# power_driver.net
KiCad netlist of a schematic drawn in EAGLE
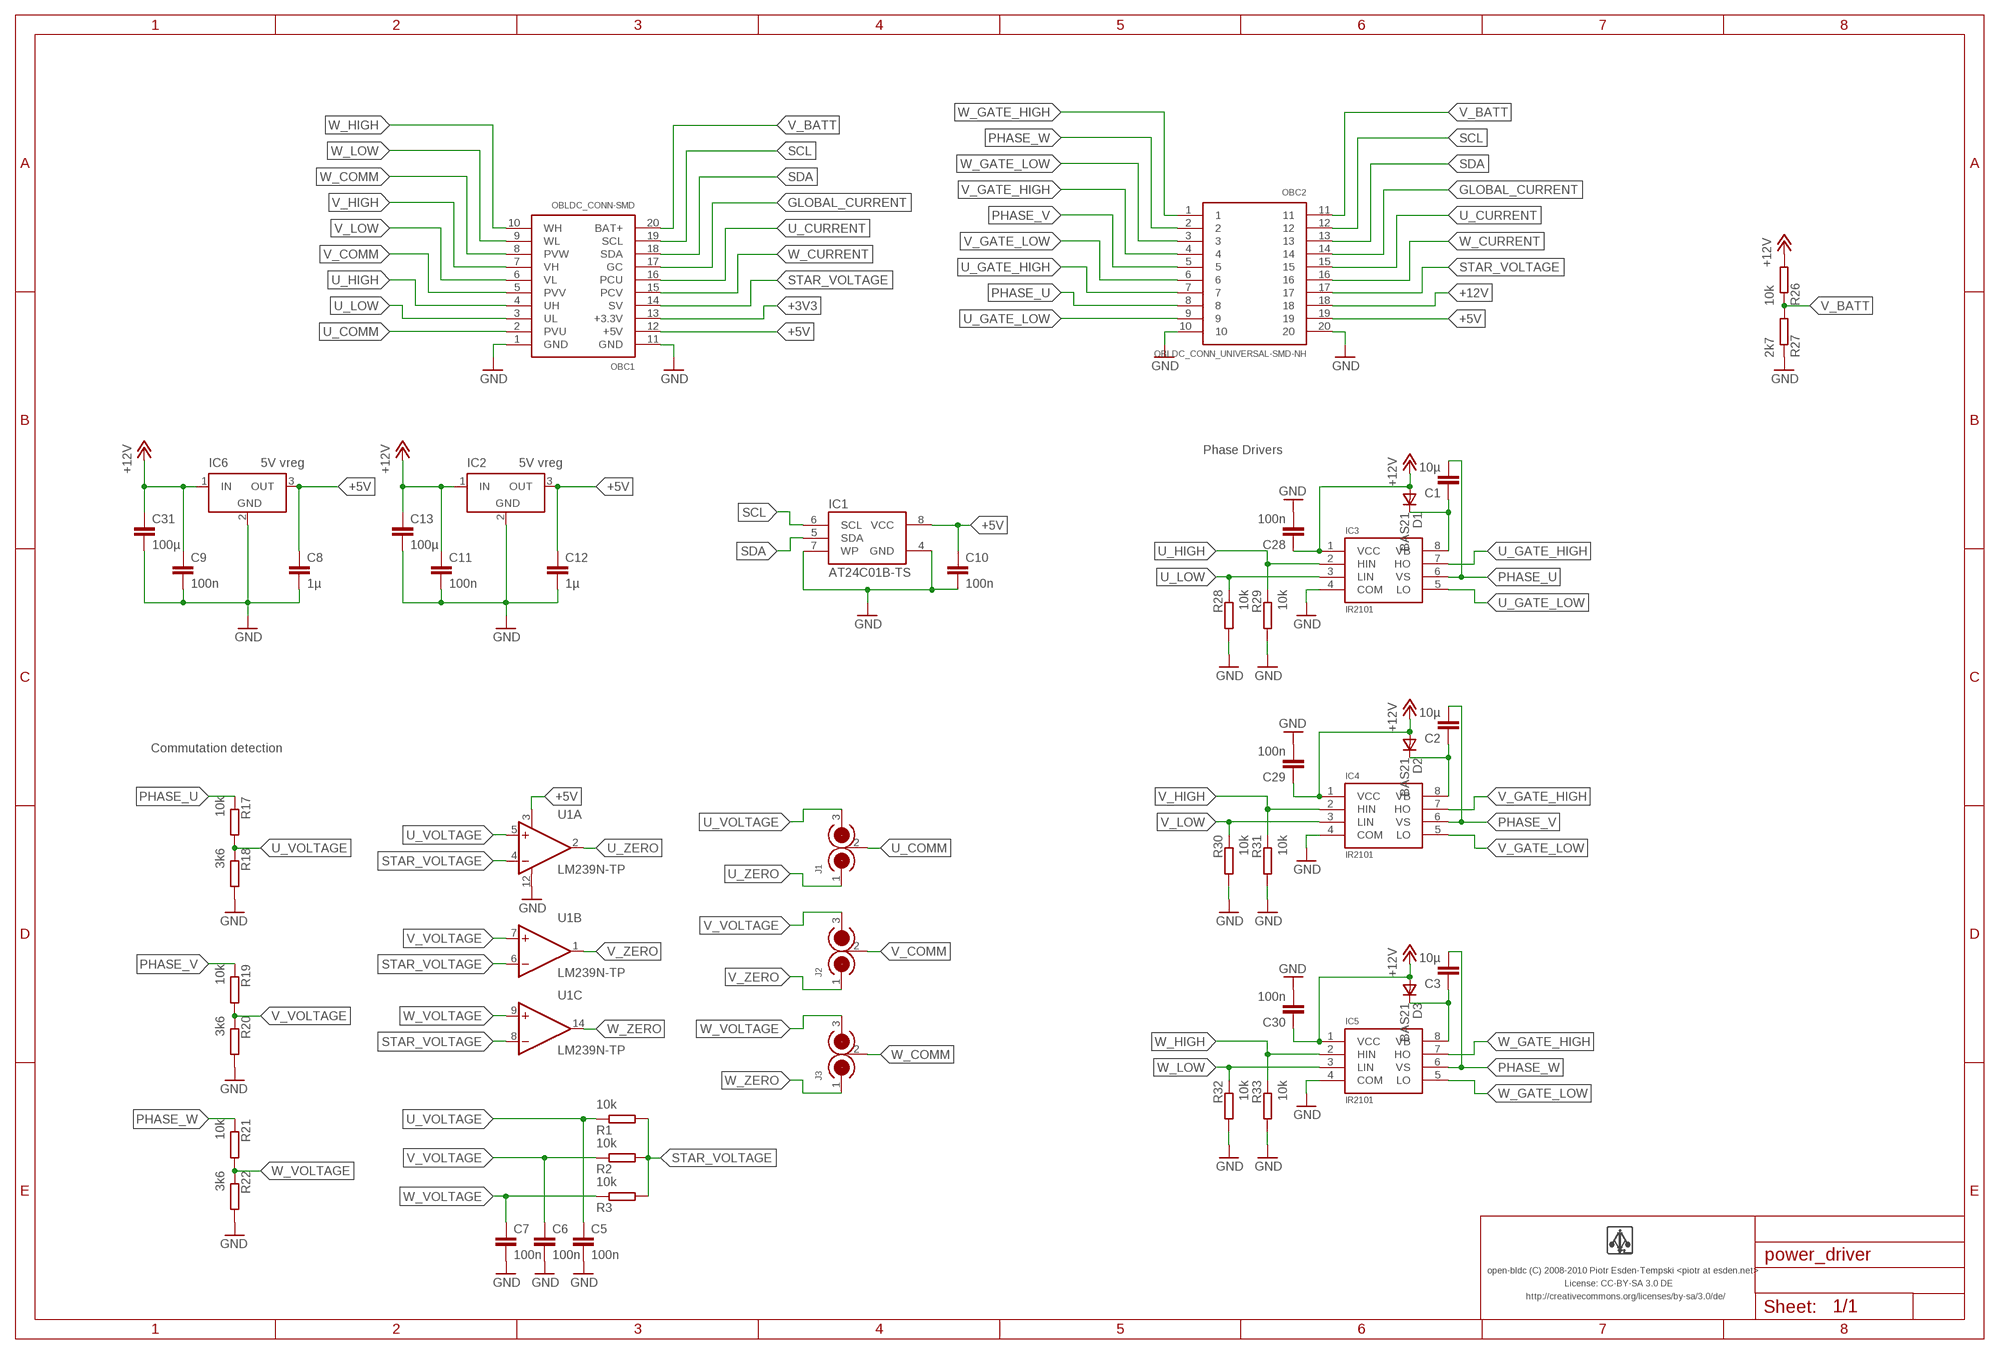
[diagram p0: schematic, sheet 1]

(export (version "E")
  (design (tool "Eeschema 10.0.6"))
  (components
    (comp (ref "C1")
      (value "10µ")
      (footprint "eagle-import:0603-CAP")
      (libsource (lib "eagle-import") (part "CAPACITOR-0603"))
    )
    (comp (ref "C2")
      (value "10µ")
      (footprint "eagle-import:0603-CAP")
      (libsource (lib "eagle-import") (part "CAPACITOR-0603"))
    )
    (comp (ref "C3")
      (value "10µ")
      (footprint "eagle-import:0603-CAP")
      (libsource (lib "eagle-import") (part "CAPACITOR-0603"))
    )
    (comp (ref "C5")
      (value "100n")
      (footprint "eagle-import:0603-CAP")
      (libsource (lib "eagle-import") (part "CAPACITOR-0603"))
    )
    (comp (ref "C6")
      (value "100n")
      (footprint "eagle-import:0603-CAP")
      (libsource (lib "eagle-import") (part "CAPACITOR-0603"))
    )
    (comp (ref "C7")
      (value "100n")
      (footprint "eagle-import:0603-CAP")
      (libsource (lib "eagle-import") (part "CAPACITOR-0603"))
    )
    (comp (ref "C8")
      (value "1µ")
      (footprint "eagle-import:0603-CAP")
      (libsource (lib "eagle-import") (part "CAPACITOR-0603"))
    )
    (comp (ref "C9")
      (value "100n")
      (footprint "eagle-import:0603-CAP")
      (libsource (lib "eagle-import") (part "CAPACITOR-0603"))
    )
    (comp (ref "C10")
      (value "100n")
      (footprint "eagle-import:0603-CAP")
      (libsource (lib "eagle-import") (part "CAPACITOR-0603"))
    )
    (comp (ref "C11")
      (value "100n")
      (footprint "eagle-import:0603-CAP")
      (libsource (lib "eagle-import") (part "CAPACITOR-0603"))
    )
    (comp (ref "C12")
      (value "1µ")
      (footprint "eagle-import:0603-CAP")
      (libsource (lib "eagle-import") (part "CAPACITOR-0603"))
    )
    (comp (ref "C13")
      (value "100µ")
      (footprint "eagle-import:0603-CAP")
      (libsource (lib "eagle-import") (part "CAPACITOR-0603"))
    )
    (comp (ref "C28")
      (value "100n")
      (footprint "eagle-import:0603-CAP")
      (libsource (lib "eagle-import") (part "CAPACITOR-0603"))
    )
    (comp (ref "C29")
      (value "100n")
      (footprint "eagle-import:0603-CAP")
      (libsource (lib "eagle-import") (part "CAPACITOR-0603"))
    )
    (comp (ref "C30")
      (value "100n")
      (footprint "eagle-import:0603-CAP")
      (libsource (lib "eagle-import") (part "CAPACITOR-0603"))
    )
    (comp (ref "C31")
      (value "100µ")
      (footprint "eagle-import:0603-CAP")
      (libsource (lib "eagle-import") (part "CAPACITOR-0603"))
    )
    (comp (ref "D1")
      (value "BAS21")
      (footprint "eagle-import:SOT-23")
      (libsource (lib "eagle-import") (part "VAR2SOT23"))
    )
    (comp (ref "D2")
      (value "BAS21")
      (footprint "eagle-import:SOT-23")
      (libsource (lib "eagle-import") (part "VAR2SOT23"))
    )
    (comp (ref "D3")
      (value "BAS21")
      (footprint "eagle-import:SOT-23")
      (libsource (lib "eagle-import") (part "VAR2SOT23"))
    )
    (comp (ref "IC1")
      (value "AT24C01B-TS")
      (footprint "eagle-import:TSSOP8")
      (libsource (lib "eagle-import") (part "AT24C01B-TS"))
    )
    (comp (ref "IC2")
      (value "5V vreg")
      (footprint "eagle-import:SOT223")
      (libsource (lib "eagle-import") (part "LT1129CST5"))
    )
    (comp (ref "IC3")
      (value "IR2101")
      (footprint "eagle-import:SO-8")
      (libsource (lib "eagle-import") (part "IR2101"))
    )
    (comp (ref "IC4")
      (value "IR2101")
      (footprint "eagle-import:SO-8")
      (libsource (lib "eagle-import") (part "IR2101"))
    )
    (comp (ref "IC5")
      (value "IR2101")
      (footprint "eagle-import:SO-8")
      (libsource (lib "eagle-import") (part "IR2101"))
    )
    (comp (ref "IC6")
      (value "5V vreg")
      (footprint "eagle-import:SOT223")
      (libsource (lib "eagle-import") (part "LT1129CST5"))
    )
    (comp (ref "J1")
      (value "CIRC_JMP_2")
      (footprint "eagle-import:CIRC_JMP_2")
      (libsource (lib "eagle-import") (part "CIRC_JMP_2"))
    )
    (comp (ref "J2")
      (value "CIRC_JMP_2")
      (footprint "eagle-import:CIRC_JMP_2")
      (libsource (lib "eagle-import") (part "CIRC_JMP_2"))
    )
    (comp (ref "J3")
      (value "CIRC_JMP_2")
      (footprint "eagle-import:CIRC_JMP_2")
      (libsource (lib "eagle-import") (part "CIRC_JMP_2"))
    )
    (comp (ref "OBC1")
      (value "OBLDC_CONN-SMD")
      (footprint "eagle-import:OBLDC_CONN_SMD")
      (libsource (lib "eagle-import") (part "OBLDC_CONN-SMD"))
    )
    (comp (ref "OBC2")
      (value "OBLDC_CONN_UNIVERSAL-SMD-NH")
      (footprint "eagle-import:OBLDC_CONN_SMD_NO_HOLES")
      (libsource (lib "eagle-import") (part "OBLDC_CONN_UNIVERSAL-SMD-NH"))
    )
    (comp (ref "R1")
      (value "10k")
      (footprint "eagle-import:0603-RES")
      (libsource (lib "eagle-import") (part "RESISTOR-0603"))
    )
    (comp (ref "R2")
      (value "10k")
      (footprint "eagle-import:0603-RES")
      (libsource (lib "eagle-import") (part "RESISTOR-0603"))
    )
    (comp (ref "R3")
      (value "10k")
      (footprint "eagle-import:0603-RES")
      (libsource (lib "eagle-import") (part "RESISTOR-0603"))
    )
    (comp (ref "R17")
      (value "10k")
      (footprint "eagle-import:0603-RES")
      (libsource (lib "eagle-import") (part "RESISTOR-0603"))
    )
    (comp (ref "R18")
      (value "3k6")
      (footprint "eagle-import:0603-RES")
      (libsource (lib "eagle-import") (part "RESISTOR-0603"))
    )
    (comp (ref "R19")
      (value "10k")
      (footprint "eagle-import:0603-RES")
      (libsource (lib "eagle-import") (part "RESISTOR-0603"))
    )
    (comp (ref "R20")
      (value "3k6")
      (footprint "eagle-import:0603-RES")
      (libsource (lib "eagle-import") (part "RESISTOR-0603"))
    )
    (comp (ref "R21")
      (value "10k")
      (footprint "eagle-import:0603-RES")
      (libsource (lib "eagle-import") (part "RESISTOR-0603"))
    )
    (comp (ref "R22")
      (value "3k6")
      (footprint "eagle-import:0603-RES")
      (libsource (lib "eagle-import") (part "RESISTOR-0603"))
    )
    (comp (ref "R26")
      (value "10k")
      (footprint "eagle-import:0603-RES")
      (libsource (lib "eagle-import") (part "RESISTOR-0603"))
    )
    (comp (ref "R27")
      (value "2k7")
      (footprint "eagle-import:0603-RES")
      (libsource (lib "eagle-import") (part "RESISTOR-0603"))
    )
    (comp (ref "R28")
      (value "10k")
      (footprint "eagle-import:0603-RES")
      (libsource (lib "eagle-import") (part "RESISTOR-0603"))
    )
    (comp (ref "R29")
      (value "10k")
      (footprint "eagle-import:0603-RES")
      (libsource (lib "eagle-import") (part "RESISTOR-0603"))
    )
    (comp (ref "R30")
      (value "10k")
      (footprint "eagle-import:0603-RES")
      (libsource (lib "eagle-import") (part "RESISTOR-0603"))
    )
    (comp (ref "R31")
      (value "10k")
      (footprint "eagle-import:0603-RES")
      (libsource (lib "eagle-import") (part "RESISTOR-0603"))
    )
    (comp (ref "R32")
      (value "10k")
      (footprint "eagle-import:0603-RES")
      (libsource (lib "eagle-import") (part "RESISTOR-0603"))
    )
    (comp (ref "R33")
      (value "10k")
      (footprint "eagle-import:0603-RES")
      (libsource (lib "eagle-import") (part "RESISTOR-0603"))
    )
    (comp (ref "U$1")
      (value "LOGO-NORM")
      (footprint "eagle-import:LOGO")
      (libsource (lib "eagle-import") (part "LOGO-NORM"))
    )
    (comp (ref "U1")
      (value "LM239N-TP")
      (footprint "eagle-import:TSSOP_14")
      (libsource (lib "eagle-import") (part "LM239N-TP"))
    )
  )
  (nets
    (net (code "1") (name "+3V3") (class "Default")
      (node (ref "OBC1") (pin "13") (pinfunction "+3.3V_13") (pintype "bidirectional"))
    )
    (net (code "2") (name "+5V") (class "Default")
      (node (ref "C10") (pin "P$1") (pinfunction "1_P$1") (pintype "passive"))
      (node (ref "C12") (pin "P$1") (pinfunction "1_P$1") (pintype "passive"))
      (node (ref "C8") (pin "P$1") (pinfunction "1_P$1") (pintype "passive"))
      (node (ref "IC1") (pin "8") (pinfunction "VCC_8") (pintype "bidirectional"))
      (node (ref "IC2") (pin "3") (pinfunction "OUT_3") (pintype "power_in"))
      (node (ref "IC6") (pin "3") (pinfunction "OUT_3") (pintype "power_in"))
      (node (ref "OBC1") (pin "12") (pinfunction "+5V_12") (pintype "bidirectional"))
      (node (ref "OBC2") (pin "19") (pinfunction "19_19") (pintype "bidirectional"))
      (node (ref "U1") (pin "3") (pinfunction "V+_3") (pintype "power_in"))
    )
    (net (code "3") (name "+12V") (class "Default")
      (node (ref "C11") (pin "P$1") (pinfunction "1_P$1") (pintype "passive"))
      (node (ref "C13") (pin "P$1") (pinfunction "1_P$1") (pintype "passive"))
      (node (ref "C28") (pin "P$1") (pinfunction "1_P$1") (pintype "passive"))
      (node (ref "C29") (pin "P$1") (pinfunction "1_P$1") (pintype "passive"))
      (node (ref "C30") (pin "P$1") (pinfunction "1_P$1") (pintype "passive"))
      (node (ref "C31") (pin "P$1") (pinfunction "1_P$1") (pintype "passive"))
      (node (ref "C9") (pin "P$1") (pinfunction "1_P$1") (pintype "passive"))
      (node (ref "D1") (pin "3") (pinfunction "A_3") (pintype "passive"))
      (node (ref "D2") (pin "3") (pinfunction "A_3") (pintype "passive"))
      (node (ref "D3") (pin "3") (pinfunction "A_3") (pintype "passive"))
      (node (ref "IC2") (pin "1") (pinfunction "IN_1") (pintype "input"))
      (node (ref "IC3") (pin "1") (pinfunction "VCC_1") (pintype "bidirectional"))
      (node (ref "IC4") (pin "1") (pinfunction "VCC_1") (pintype "bidirectional"))
      (node (ref "IC5") (pin "1") (pinfunction "VCC_1") (pintype "bidirectional"))
      (node (ref "IC6") (pin "1") (pinfunction "IN_1") (pintype "input"))
      (node (ref "OBC2") (pin "18") (pinfunction "18_18") (pintype "bidirectional"))
      (node (ref "R26") (pin "P$2") (pinfunction "2_P$2") (pintype "passive"))
    )
    (net (code "4") (name "GLOBAL_CURRENT") (class "Default")
      (node (ref "OBC1") (pin "17") (pinfunction "GC_17") (pintype "bidirectional"))
      (node (ref "OBC2") (pin "14") (pinfunction "14_14") (pintype "bidirectional"))
    )
    (net (code "5") (name "GND") (class "Default")
      (node (ref "C10") (pin "P$2") (pinfunction "2_P$2") (pintype "passive"))
      (node (ref "C11") (pin "P$2") (pinfunction "2_P$2") (pintype "passive"))
      (node (ref "C12") (pin "P$2") (pinfunction "2_P$2") (pintype "passive"))
      (node (ref "C13") (pin "P$2") (pinfunction "2_P$2") (pintype "passive"))
      (node (ref "C28") (pin "P$2") (pinfunction "2_P$2") (pintype "passive"))
      (node (ref "C29") (pin "P$2") (pinfunction "2_P$2") (pintype "passive"))
      (node (ref "C30") (pin "P$2") (pinfunction "2_P$2") (pintype "passive"))
      (node (ref "C31") (pin "P$2") (pinfunction "2_P$2") (pintype "passive"))
      (node (ref "C5") (pin "P$2") (pinfunction "2_P$2") (pintype "passive"))
      (node (ref "C6") (pin "P$2") (pinfunction "2_P$2") (pintype "passive"))
      (node (ref "C7") (pin "P$2") (pinfunction "2_P$2") (pintype "passive"))
      (node (ref "C8") (pin "P$2") (pinfunction "2_P$2") (pintype "passive"))
      (node (ref "C9") (pin "P$2") (pinfunction "2_P$2") (pintype "passive"))
      (node (ref "IC1") (pin "4") (pinfunction "GND_4") (pintype "bidirectional"))
      (node (ref "IC1") (pin "7") (pinfunction "WP_7") (pintype "bidirectional"))
      (node (ref "IC2") (pin "2") (pinfunction "GND_2") (pintype "power_in"))
      (node (ref "IC3") (pin "4") (pinfunction "COM_4") (pintype "bidirectional"))
      (node (ref "IC4") (pin "4") (pinfunction "COM_4") (pintype "bidirectional"))
      (node (ref "IC5") (pin "4") (pinfunction "COM_4") (pintype "bidirectional"))
      (node (ref "IC6") (pin "2") (pinfunction "GND_2") (pintype "power_in"))
      (node (ref "OBC1") (pin "1") (pinfunction "GND_1") (pintype "bidirectional"))
      (node (ref "OBC1") (pin "11") (pinfunction "GND_11") (pintype "bidirectional"))
      (node (ref "OBC2") (pin "10") (pinfunction "10_10") (pintype "bidirectional"))
      (node (ref "OBC2") (pin "20") (pinfunction "20_20") (pintype "bidirectional"))
      (node (ref "R18") (pin "P$2") (pinfunction "2_P$2") (pintype "passive"))
      (node (ref "R20") (pin "P$2") (pinfunction "2_P$2") (pintype "passive"))
      (node (ref "R22") (pin "P$2") (pinfunction "2_P$2") (pintype "passive"))
      (node (ref "R27") (pin "P$1") (pinfunction "1_P$1") (pintype "passive"))
      (node (ref "R28") (pin "P$2") (pinfunction "2_P$2") (pintype "passive"))
      (node (ref "R29") (pin "P$2") (pinfunction "2_P$2") (pintype "passive"))
      (node (ref "R30") (pin "P$2") (pinfunction "2_P$2") (pintype "passive"))
      (node (ref "R31") (pin "P$2") (pinfunction "2_P$2") (pintype "passive"))
      (node (ref "R32") (pin "P$2") (pinfunction "2_P$2") (pintype "passive"))
      (node (ref "R33") (pin "P$2") (pinfunction "2_P$2") (pintype "passive"))
      (node (ref "U1") (pin "12") (pinfunction "V-_12") (pintype "power_in"))
    )
    (net (code "6") (name "Net-(C1-1)") (class "Default")
      (node (ref "C1") (pin "P$1") (pinfunction "1_P$1") (pintype "passive"))
      (node (ref "D1") (pin "1") (pinfunction "C_1") (pintype "passive"))
      (node (ref "IC3") (pin "8") (pinfunction "VB_8") (pintype "bidirectional"))
    )
    (net (code "7") (name "Net-(C2-1)") (class "Default")
      (node (ref "C2") (pin "P$1") (pinfunction "1_P$1") (pintype "passive"))
      (node (ref "D2") (pin "1") (pinfunction "C_1") (pintype "passive"))
      (node (ref "IC4") (pin "8") (pinfunction "VB_8") (pintype "bidirectional"))
    )
    (net (code "8") (name "Net-(C3-1)") (class "Default")
      (node (ref "C3") (pin "P$1") (pinfunction "1_P$1") (pintype "passive"))
      (node (ref "D3") (pin "1") (pinfunction "C_1") (pintype "passive"))
      (node (ref "IC5") (pin "8") (pinfunction "VB_8") (pintype "bidirectional"))
    )
    (net (code "9") (name "PHASE_U") (class "Default")
      (node (ref "C1") (pin "P$2") (pinfunction "2_P$2") (pintype "passive"))
      (node (ref "IC3") (pin "6") (pinfunction "VS_6") (pintype "bidirectional"))
      (node (ref "OBC2") (pin "8") (pinfunction "8_8") (pintype "bidirectional"))
      (node (ref "R17") (pin "P$1") (pinfunction "1_P$1") (pintype "passive"))
    )
    (net (code "10") (name "PHASE_V") (class "Default")
      (node (ref "C2") (pin "P$2") (pinfunction "2_P$2") (pintype "passive"))
      (node (ref "IC4") (pin "6") (pinfunction "VS_6") (pintype "bidirectional"))
      (node (ref "OBC2") (pin "5") (pinfunction "5_5") (pintype "bidirectional"))
      (node (ref "R19") (pin "P$1") (pinfunction "1_P$1") (pintype "passive"))
    )
    (net (code "11") (name "PHASE_W") (class "Default")
      (node (ref "C3") (pin "P$2") (pinfunction "2_P$2") (pintype "passive"))
      (node (ref "IC5") (pin "6") (pinfunction "VS_6") (pintype "bidirectional"))
      (node (ref "OBC2") (pin "2") (pinfunction "2_2") (pintype "bidirectional"))
      (node (ref "R21") (pin "P$1") (pinfunction "1_P$1") (pintype "passive"))
    )
    (net (code "12") (name "SCL") (class "Default")
      (node (ref "IC1") (pin "6") (pinfunction "SCL_6") (pintype "bidirectional"))
      (node (ref "OBC1") (pin "19") (pinfunction "SCL_19") (pintype "bidirectional"))
      (node (ref "OBC2") (pin "12") (pinfunction "12_12") (pintype "bidirectional"))
    )
    (net (code "13") (name "SDA") (class "Default")
      (node (ref "IC1") (pin "5") (pinfunction "SDA_5") (pintype "bidirectional"))
      (node (ref "OBC1") (pin "18") (pinfunction "SDA_18") (pintype "bidirectional"))
      (node (ref "OBC2") (pin "13") (pinfunction "13_13") (pintype "bidirectional"))
    )
    (net (code "14") (name "STAR_VOLTAGE") (class "Default")
      (node (ref "OBC1") (pin "14") (pinfunction "SV_14") (pintype "bidirectional"))
      (node (ref "OBC2") (pin "17") (pinfunction "17_17") (pintype "bidirectional"))
      (node (ref "R1") (pin "P$2") (pinfunction "2_P$2") (pintype "passive"))
      (node (ref "R2") (pin "P$2") (pinfunction "2_P$2") (pintype "passive"))
      (node (ref "R3") (pin "P$2") (pinfunction "2_P$2") (pintype "passive"))
      (node (ref "U1") (pin "4") (pinfunction "-IN_4") (pintype "input"))
      (node (ref "U1") (pin "6") (pinfunction "-IN_6") (pintype "input"))
      (node (ref "U1") (pin "8") (pinfunction "-IN_8") (pintype "input"))
    )
    (net (code "15") (name "U_COMM") (class "Default")
      (node (ref "J1") (pin "2") (pinfunction "P$2_2") (pintype "bidirectional"))
      (node (ref "OBC1") (pin "2") (pinfunction "PVU_2") (pintype "bidirectional"))
    )
    (net (code "16") (name "U_CURRENT") (class "Default")
      (node (ref "OBC1") (pin "16") (pinfunction "PCU_16") (pintype "bidirectional"))
      (node (ref "OBC2") (pin "15") (pinfunction "15_15") (pintype "bidirectional"))
    )
    (net (code "17") (name "U_GATE_HIGH") (class "Default")
      (node (ref "IC3") (pin "7") (pinfunction "HO_7") (pintype "bidirectional"))
      (node (ref "OBC2") (pin "7") (pinfunction "7_7") (pintype "bidirectional"))
    )
    (net (code "18") (name "U_GATE_LOW") (class "Default")
      (node (ref "IC3") (pin "5") (pinfunction "LO_5") (pintype "bidirectional"))
      (node (ref "OBC2") (pin "9") (pinfunction "9_9") (pintype "bidirectional"))
    )
    (net (code "19") (name "U_HIGH") (class "Default")
      (node (ref "IC3") (pin "2") (pinfunction "HIN_2") (pintype "bidirectional"))
      (node (ref "OBC1") (pin "4") (pinfunction "UH_4") (pintype "bidirectional"))
      (node (ref "R29") (pin "P$1") (pinfunction "1_P$1") (pintype "passive"))
    )
    (net (code "20") (name "U_LOW") (class "Default")
      (node (ref "IC3") (pin "3") (pinfunction "LIN_3") (pintype "bidirectional"))
      (node (ref "OBC1") (pin "3") (pinfunction "UL_3") (pintype "bidirectional"))
      (node (ref "R28") (pin "P$1") (pinfunction "1_P$1") (pintype "passive"))
    )
    (net (code "21") (name "U_VOLTAGE") (class "Default")
      (node (ref "C5") (pin "P$1") (pinfunction "1_P$1") (pintype "passive"))
      (node (ref "J1") (pin "3") (pinfunction "P$3_3") (pintype "bidirectional"))
      (node (ref "R1") (pin "P$1") (pinfunction "1_P$1") (pintype "passive"))
      (node (ref "R17") (pin "P$2") (pinfunction "2_P$2") (pintype "passive"))
      (node (ref "R18") (pin "P$1") (pinfunction "1_P$1") (pintype "passive"))
      (node (ref "U1") (pin "5") (pinfunction "+IN_5") (pintype "input"))
    )
    (net (code "22") (name "U_ZERO") (class "Default")
      (node (ref "J1") (pin "1") (pinfunction "P$1_1") (pintype "bidirectional"))
      (node (ref "U1") (pin "2") (pinfunction "OUT_2") (pintype "output"))
    )
    (net (code "23") (name "V_BATT") (class "Default")
      (node (ref "OBC1") (pin "20") (pinfunction "BAT+_20") (pintype "bidirectional"))
      (node (ref "OBC2") (pin "11") (pinfunction "11_11") (pintype "bidirectional"))
      (node (ref "R26") (pin "P$1") (pinfunction "1_P$1") (pintype "passive"))
      (node (ref "R27") (pin "P$2") (pinfunction "2_P$2") (pintype "passive"))
    )
    (net (code "24") (name "V_COMM") (class "Default")
      (node (ref "J2") (pin "2") (pinfunction "P$2_2") (pintype "bidirectional"))
      (node (ref "OBC1") (pin "5") (pinfunction "PVV_5") (pintype "bidirectional"))
    )
    (net (code "25") (name "V_GATE_HIGH") (class "Default")
      (node (ref "IC4") (pin "7") (pinfunction "HO_7") (pintype "bidirectional"))
      (node (ref "OBC2") (pin "4") (pinfunction "4_4") (pintype "bidirectional"))
    )
    (net (code "26") (name "V_GATE_LOW") (class "Default")
      (node (ref "IC4") (pin "5") (pinfunction "LO_5") (pintype "bidirectional"))
      (node (ref "OBC2") (pin "6") (pinfunction "6_6") (pintype "bidirectional"))
    )
    (net (code "27") (name "V_HIGH") (class "Default")
      (node (ref "IC4") (pin "2") (pinfunction "HIN_2") (pintype "bidirectional"))
      (node (ref "OBC1") (pin "7") (pinfunction "VH_7") (pintype "bidirectional"))
      (node (ref "R31") (pin "P$1") (pinfunction "1_P$1") (pintype "passive"))
    )
    (net (code "28") (name "V_LOW") (class "Default")
      (node (ref "IC4") (pin "3") (pinfunction "LIN_3") (pintype "bidirectional"))
      (node (ref "OBC1") (pin "6") (pinfunction "VL_6") (pintype "bidirectional"))
      (node (ref "R30") (pin "P$1") (pinfunction "1_P$1") (pintype "passive"))
    )
    (net (code "29") (name "V_VOLTAGE") (class "Default")
      (node (ref "C6") (pin "P$1") (pinfunction "1_P$1") (pintype "passive"))
      (node (ref "J2") (pin "3") (pinfunction "P$3_3") (pintype "bidirectional"))
      (node (ref "R19") (pin "P$2") (pinfunction "2_P$2") (pintype "passive"))
      (node (ref "R2") (pin "P$1") (pinfunction "1_P$1") (pintype "passive"))
      (node (ref "R20") (pin "P$1") (pinfunction "1_P$1") (pintype "passive"))
      (node (ref "U1") (pin "7") (pinfunction "+IN_7") (pintype "input"))
    )
    (net (code "30") (name "V_ZERO") (class "Default")
      (node (ref "J2") (pin "1") (pinfunction "P$1_1") (pintype "bidirectional"))
      (node (ref "U1") (pin "1") (pinfunction "OUT_1") (pintype "output"))
    )
    (net (code "31") (name "W_COMM") (class "Default")
      (node (ref "J3") (pin "2") (pinfunction "P$2_2") (pintype "bidirectional"))
      (node (ref "OBC1") (pin "8") (pinfunction "PVW_8") (pintype "bidirectional"))
    )
    (net (code "32") (name "W_CURRENT") (class "Default")
      (node (ref "OBC1") (pin "15") (pinfunction "PCV_15") (pintype "bidirectional"))
      (node (ref "OBC2") (pin "16") (pinfunction "16_16") (pintype "bidirectional"))
    )
    (net (code "33") (name "W_GATE_HIGH") (class "Default")
      (node (ref "IC5") (pin "7") (pinfunction "HO_7") (pintype "bidirectional"))
      (node (ref "OBC2") (pin "1") (pinfunction "1_1") (pintype "bidirectional"))
    )
    (net (code "34") (name "W_GATE_LOW") (class "Default")
      (node (ref "IC5") (pin "5") (pinfunction "LO_5") (pintype "bidirectional"))
      (node (ref "OBC2") (pin "3") (pinfunction "3_3") (pintype "bidirectional"))
    )
    (net (code "35") (name "W_HIGH") (class "Default")
      (node (ref "IC5") (pin "2") (pinfunction "HIN_2") (pintype "bidirectional"))
      (node (ref "OBC1") (pin "10") (pinfunction "WH_10") (pintype "bidirectional"))
      (node (ref "R33") (pin "P$1") (pinfunction "1_P$1") (pintype "passive"))
    )
    (net (code "36") (name "W_LOW") (class "Default")
      (node (ref "IC5") (pin "3") (pinfunction "LIN_3") (pintype "bidirectional"))
      (node (ref "OBC1") (pin "9") (pinfunction "WL_9") (pintype "bidirectional"))
      (node (ref "R32") (pin "P$1") (pinfunction "1_P$1") (pintype "passive"))
    )
    (net (code "37") (name "W_VOLTAGE") (class "Default")
      (node (ref "C7") (pin "P$1") (pinfunction "1_P$1") (pintype "passive"))
      (node (ref "J3") (pin "3") (pinfunction "P$3_3") (pintype "bidirectional"))
      (node (ref "R21") (pin "P$2") (pinfunction "2_P$2") (pintype "passive"))
      (node (ref "R22") (pin "P$1") (pinfunction "1_P$1") (pintype "passive"))
      (node (ref "R3") (pin "P$1") (pinfunction "1_P$1") (pintype "passive"))
      (node (ref "U1") (pin "9") (pinfunction "+IN_9") (pintype "input"))
    )
    (net (code "38") (name "W_ZERO") (class "Default")
      (node (ref "J3") (pin "1") (pinfunction "P$1_1") (pintype "bidirectional"))
      (node (ref "U1") (pin "14") (pinfunction "OUT_14") (pintype "output"))
    )
  )
)
